# 07-multimodal-microcontroller-oscillator.net
KiCad netlist of a schematic drawn in Altium Designer
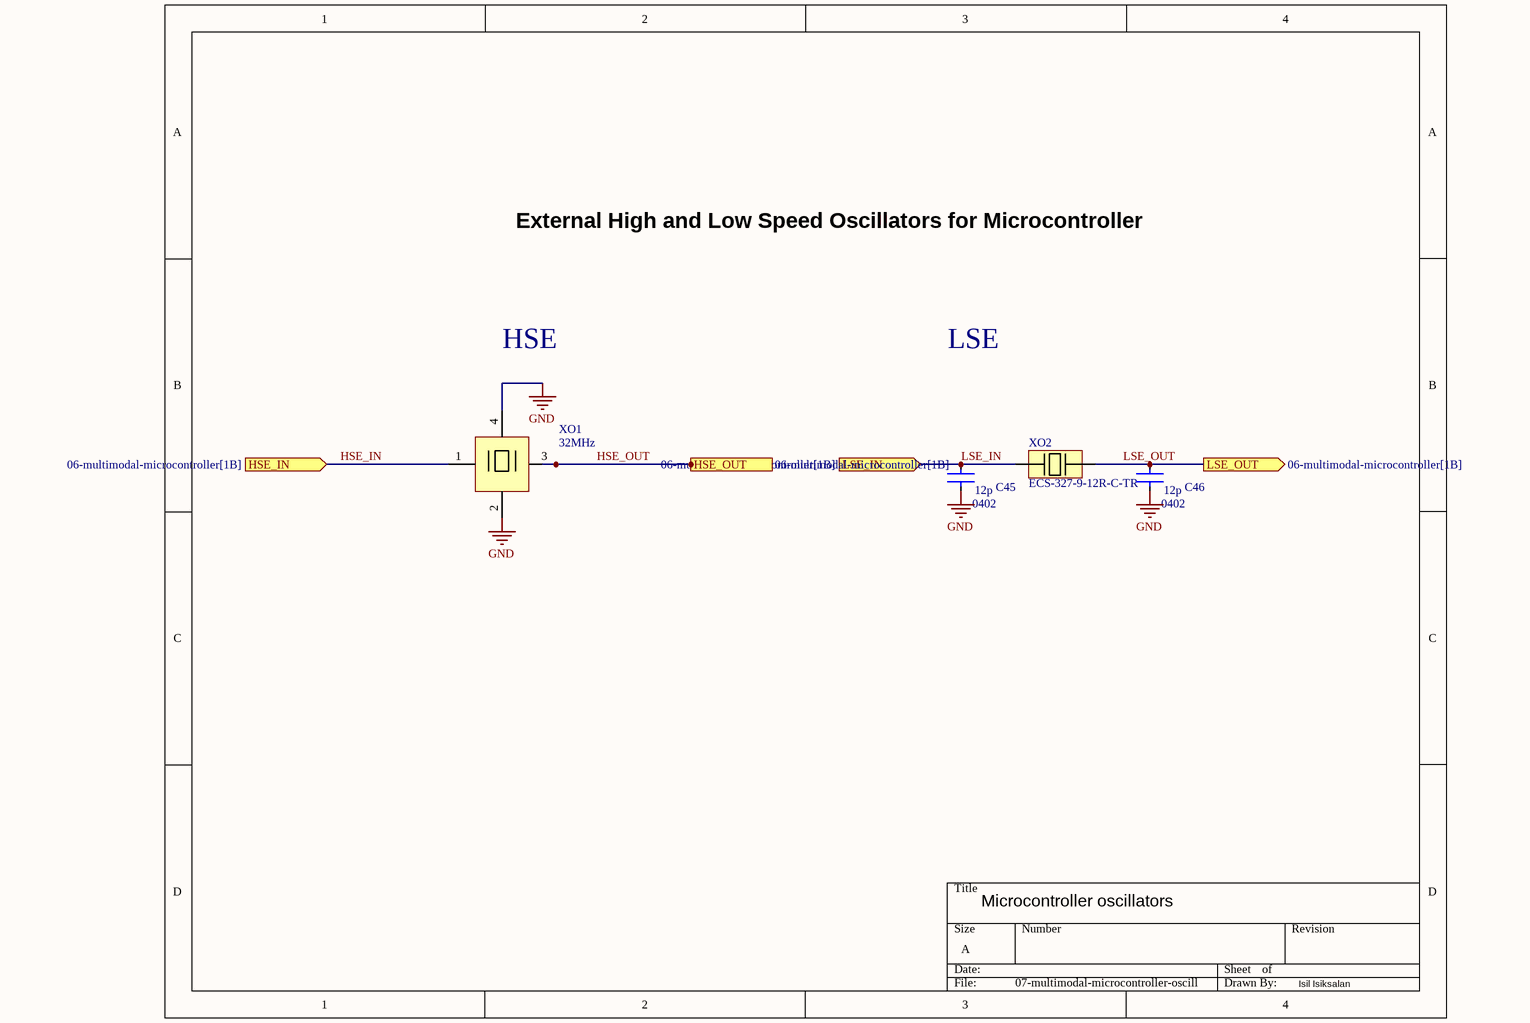
[diagram p0: 07-multimodal-microcontroller-oscillators.SchDoc]

(export (version "E")
  (design (tool "Eeschema 10.0.6"))
  (components
    (comp (ref "C45")
      (value "CGA2B2C0G1H120J050BA")
      (footprint "CAPTDK0402")
      (description "CAP CER 12PF 50V C0G 0402")
      (libsource (lib "multimodal") (part "CGA2B2C0G1H120J050BA"))
    )
    (comp (ref "C46")
      (value "CGA2B2C0G1H120J050BA")
      (footprint "CAPTDK0402")
      (description "CAP CER 12PF 50V C0G 0402")
      (libsource (lib "multimodal") (part "CGA2B2C0G1H120J050BA"))
    )
    (comp (ref "XO1")
      (value "32MHz")
      (footprint "HSE-32MHZ")
      (description "CRYSTAL 32MHZ 8PF 60R SMD")
      (fields
        (field (name "MANUFACTURER") "NDK")
        (field (name "MANUFACTURER PART NUMBER") "NX2016SA-32MHZ-EXS00A-CS06654")
      )
      (libsource (lib "multimodal") (part "NX2016SA-32MHZ-EXS00A-CS06654"))
    )
    (comp (ref "XO2")
      (value "ECS-327-9-12R-C-TR")
      (footprint "LSE-32K")
      (description "Crystal 0.032768MHz ±10ppm (Tol) 9pF Flexural 70000Ohm Automotive 2-Pin Ultra Mini-CSMD T/R")
      (fields
        (field (name "MANUFACTURER") "ECS International")
        (field (name "MANUFACTURER PART NUMBER") "ECS-.327-9-12R-C-TR")
      )
      (libsource (lib "multimodal") (part "ECS-327-9-12R-C-TR"))
    )
  )
  (nets
    (net (code "1") (name "/HSE_IN") (class "Default")
      (node (ref "XO1") (pin "1") (pinfunction "1_1") (pintype "passive"))
    )
    (net (code "2") (name "/HSE_OUT") (class "Default")
      (node (ref "XO1") (pin "3") (pinfunction "3_3") (pintype "passive"))
    )
    (net (code "3") (name "/LSE_IN") (class "Default")
      (node (ref "C45") (pin "1") (pinfunction "1_1") (pintype "passive"))
      (node (ref "XO2") (pin "1") (pinfunction "1_1") (pintype "passive"))
    )
    (net (code "4") (name "/LSE_OUT") (class "Default")
      (node (ref "C46") (pin "1") (pinfunction "1_1") (pintype "passive"))
      (node (ref "XO2") (pin "2") (pinfunction "2_2") (pintype "passive"))
    )
    (net (code "5") (name "GND") (class "Default")
      (node (ref "C45") (pin "2") (pinfunction "2_2") (pintype "passive"))
      (node (ref "C46") (pin "2") (pinfunction "2_2") (pintype "passive"))
      (node (ref "XO1") (pin "2") (pinfunction "2_2") (pintype "passive"))
      (node (ref "XO1") (pin "4") (pinfunction "4_4") (pintype "passive"))
    )
  )
)
